# MW5500.net
KiCad netlist of a schematic drawn in Altium Designer
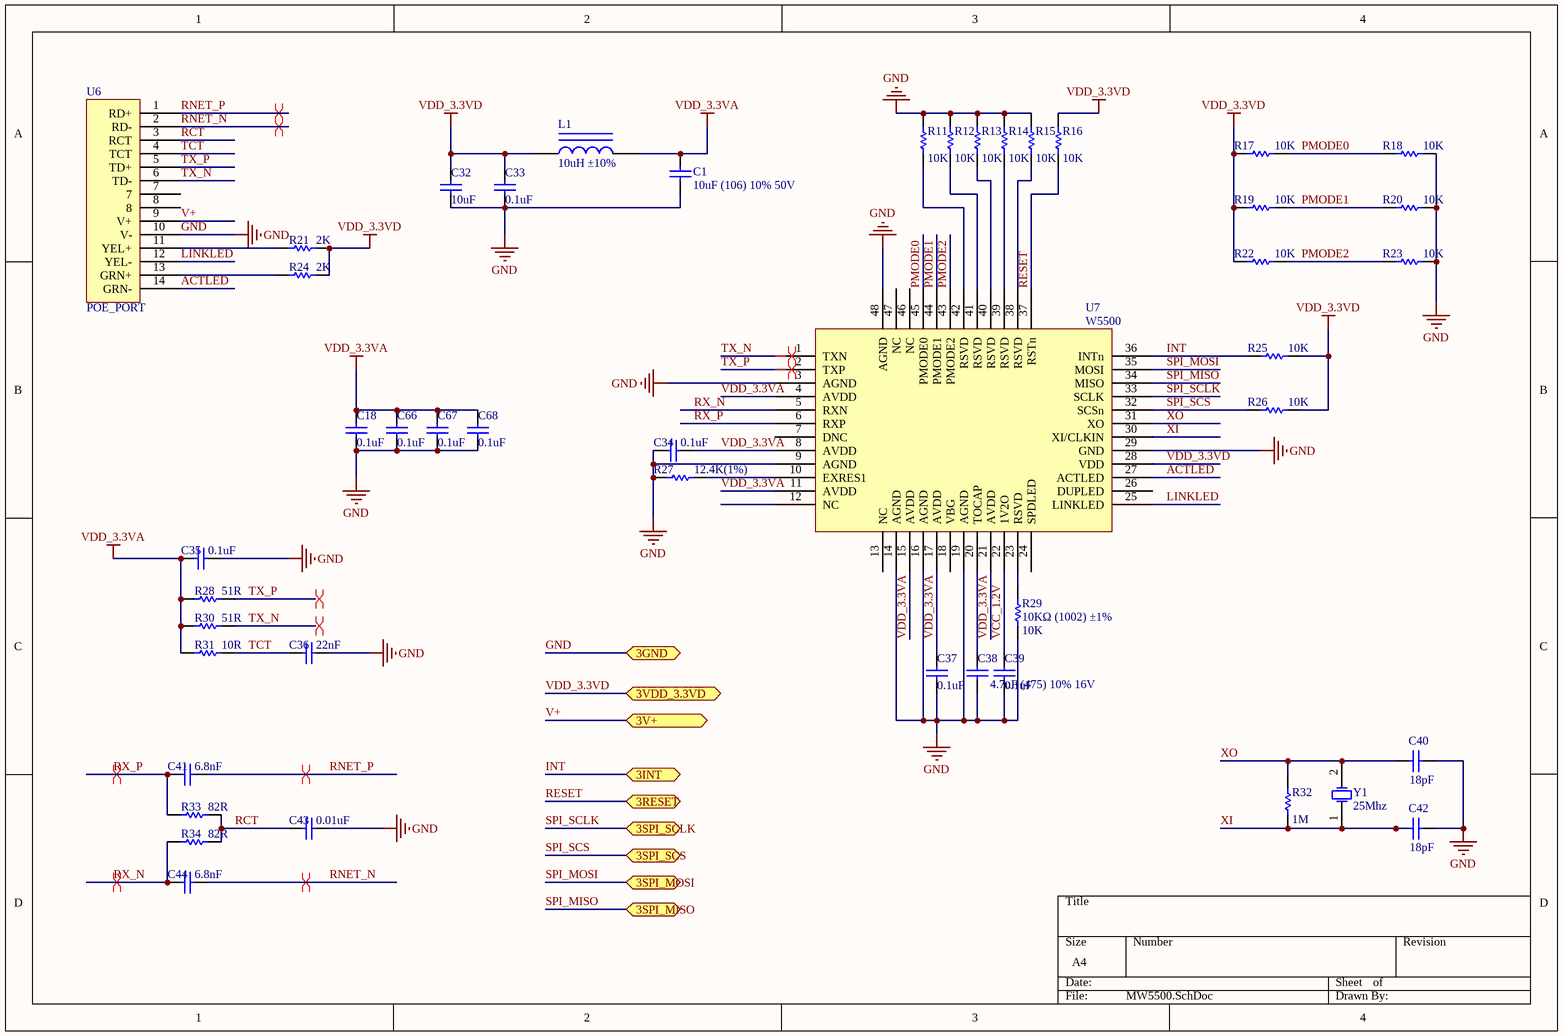
[diagram p0: MW5500.SchDoc]

(export (version "E")
  (design (tool "Eeschema 10.0.6"))
  (components
    (comp (ref "C1")
      (value "10uF (106) 10% 50V")
      (footprint "1206_C")
      (description "贴片电容")
      (libsource (lib "Miscellaneous Devices LC") (part "1206 10uF (106) 10% 50V"))
    )
    (comp (ref "C18")
      (value "0.1uF")
      (footprint "1608[0603]")
      (description "Capacitor")
      (fields (field (name "Comment") "100nF (104) ±10% 50V") (field (name "PUBLISHER") "Altium Limited"))
      (libsource (lib "Miscellaneous Devices") (part "Cap"))
    )
    (comp (ref "C32")
      (value "10uF")
      (footprint "C1206")
      (description "Capacitor")
      (fields (field (name "Comment") "10uF (106) ±10% 50V") (field (name "PUBLISHER") "Altium Limited"))
      (libsource (lib "Miscellaneous Devices") (part "Cap"))
    )
    (comp (ref "C33")
      (value "0.1uF")
      (footprint "1608[0603]")
      (description "Capacitor")
      (fields (field (name "Comment") "100nF (104) ±10% 50V") (field (name "PUBLISHER") "Altium Limited"))
      (libsource (lib "Miscellaneous Devices") (part "Cap"))
    )
    (comp (ref "C34")
      (value "0.1uF")
      (footprint "0805_C")
      (description "Capacitor")
      (fields (field (name "Comment") "100nF (104) ±10% 50V") (field (name "PUBLISHER") "Altium Limited"))
      (libsource (lib "Miscellaneous Devices") (part "Cap"))
    )
    (comp (ref "C35")
      (value "0.1uF")
      (footprint "1608[0603]")
      (description "Capacitor")
      (fields (field (name "Comment") "100nF (104) ±10% 50V") (field (name "PUBLISHER") "Altium Limited"))
      (libsource (lib "Miscellaneous Devices") (part "Cap"))
    )
    (comp (ref "C36")
      (value "22nF")
      (footprint "1608[0603]")
      (description "Capacitor")
      (fields (field (name "Comment") "22nF ±10% 50V") (field (name "PUBLISHER") "Altium Limited"))
      (libsource (lib "Miscellaneous Devices") (part "Cap"))
    )
    (comp (ref "C37")
      (value "0.1uF")
      (footprint "1608[0603]")
      (description "Capacitor")
      (fields (field (name "Comment") "100nF (104) ±10% 50V") (field (name "PUBLISHER") "Altium Limited"))
      (libsource (lib "Miscellaneous Devices") (part "Cap"))
    )
    (comp (ref "C38")
      (value "4.7uF (475) 10% 16V")
      (footprint "0603_C")
      (description "贴片电容")
      (libsource (lib "Miscellaneous Devices LC") (part "0603 4.7uF (475) 10% 16V"))
    )
    (comp (ref "C39")
      (value "0.1uF")
      (footprint "1608[0603]")
      (description "Capacitor")
      (fields (field (name "Comment") "100nF (104) ±10% 50V") (field (name "PUBLISHER") "Altium Limited"))
      (libsource (lib "Miscellaneous Devices") (part "Cap"))
    )
    (comp (ref "C40")
      (value "18pF")
      (footprint "1608[0603]")
      (description "Capacitor")
      (fields (field (name "Comment") "18pF ±10% 50V") (field (name "PUBLISHER") "Altium Limited"))
      (libsource (lib "Miscellaneous Devices") (part "Cap"))
    )
    (comp (ref "C41")
      (value "6.8nF")
      (footprint "1608[0603]")
      (description "Capacitor")
      (fields (field (name "Comment") "6.8nF ±10% 50V") (field (name "PUBLISHER") "Altium Limited"))
      (libsource (lib "Miscellaneous Devices") (part "Cap"))
    )
    (comp (ref "C42")
      (value "18pF")
      (footprint "1608[0603]")
      (description "Capacitor")
      (fields (field (name "Comment") "18pF ±10% 50V") (field (name "PUBLISHER") "Altium Limited"))
      (libsource (lib "Miscellaneous Devices") (part "Cap"))
    )
    (comp (ref "C43")
      (value "0.01uF")
      (footprint "1608[0603]")
      (description "Capacitor")
      (fields (field (name "Comment") "100nF (104) ±10% 50V") (field (name "PUBLISHER") "Altium Limited"))
      (libsource (lib "Miscellaneous Devices") (part "Cap"))
    )
    (comp (ref "C44")
      (value "6.8nF")
      (footprint "1608[0603]")
      (description "Capacitor")
      (fields (field (name "Comment") "6.8nF ±10% 50V") (field (name "PUBLISHER") "Altium Limited"))
      (libsource (lib "Miscellaneous Devices") (part "Cap"))
    )
    (comp (ref "C66")
      (value "0.1uF")
      (footprint "1608[0603]")
      (description "Capacitor")
      (fields (field (name "Comment") "100nF (104) ±10% 50V") (field (name "PUBLISHER") "Altium Limited"))
      (libsource (lib "Miscellaneous Devices") (part "Cap"))
    )
    (comp (ref "C67")
      (value "0.1uF")
      (footprint "1608[0603]")
      (description "Capacitor")
      (fields (field (name "Comment") "100nF (104) ±10% 50V") (field (name "PUBLISHER") "Altium Limited"))
      (libsource (lib "Miscellaneous Devices") (part "Cap"))
    )
    (comp (ref "C68")
      (value "0.1uF")
      (footprint "1608[0603]")
      (description "Capacitor")
      (fields (field (name "Comment") "100nF (104) ±10% 50V") (field (name "PUBLISHER") "Altium Limited"))
      (libsource (lib "Miscellaneous Devices") (part "Cap"))
    )
    (comp (ref "L1")
      (value "10uH ±10%")
      (footprint "1206_L")
      (description "贴片电感")
      (libsource (lib "Miscellaneous Devices LC") (part "1206 10uH 10%"))
    )
    (comp (ref "R11")
      (value "10K")
      (footprint "1608[0603]")
      (description "Resistor")
      (fields (field (name "Comment") "10KΩ (1002) ±1%") (field (name "PUBLISHER") "Altium Limited"))
      (libsource (lib "Miscellaneous Devices") (part "Res1"))
    )
    (comp (ref "R12")
      (value "10K")
      (footprint "1608[0603]")
      (description "Resistor")
      (fields (field (name "Comment") "10KΩ (1002) ±1%") (field (name "PUBLISHER") "Altium Limited"))
      (libsource (lib "Miscellaneous Devices") (part "Res1"))
    )
    (comp (ref "R13")
      (value "10K")
      (footprint "1608[0603]")
      (description "Resistor")
      (fields (field (name "Comment") "10KΩ (1002) ±1%") (field (name "PUBLISHER") "Altium Limited"))
      (libsource (lib "Miscellaneous Devices") (part "Res1"))
    )
    (comp (ref "R14")
      (value "10K")
      (footprint "1608[0603]")
      (description "Resistor")
      (fields (field (name "Comment") "10KΩ (1002) ±1%") (field (name "PUBLISHER") "Altium Limited"))
      (libsource (lib "Miscellaneous Devices") (part "Res1"))
    )
    (comp (ref "R15")
      (value "10K")
      (footprint "1608[0603]")
      (description "Resistor")
      (fields (field (name "Comment") "10KΩ (1002) ±1%") (field (name "PUBLISHER") "Altium Limited"))
      (libsource (lib "Miscellaneous Devices") (part "Res1"))
    )
    (comp (ref "R16")
      (value "10K")
      (footprint "1608[0603]")
      (description "Resistor")
      (fields (field (name "Comment") "10KΩ (1002) ±1%") (field (name "PUBLISHER") "Altium Limited"))
      (libsource (lib "Miscellaneous Devices") (part "Res1"))
    )
    (comp (ref "R17")
      (value "10K")
      (footprint "1608[0603]")
      (description "Resistor")
      (fields (field (name "Comment") "10KΩ (1002) ±1%") (field (name "PUBLISHER") "Altium Limited"))
      (libsource (lib "Miscellaneous Devices") (part "Res1"))
    )
    (comp (ref "R18")
      (value "10K")
      (footprint "1608[0603]")
      (description "Resistor")
      (fields (field (name "Comment") "10KΩ (1002) ±1%") (field (name "PUBLISHER") "Altium Limited"))
      (libsource (lib "Miscellaneous Devices") (part "Res1"))
    )
    (comp (ref "R19")
      (value "10K")
      (footprint "1608[0603]")
      (description "Resistor")
      (fields (field (name "Comment") "10KΩ (1002) ±1%") (field (name "PUBLISHER") "Altium Limited"))
      (libsource (lib "Miscellaneous Devices") (part "Res1"))
    )
    (comp (ref "R20")
      (value "10K")
      (footprint "1608[0603]")
      (description "Resistor")
      (fields (field (name "Comment") "10KΩ (1002) ±1%") (field (name "PUBLISHER") "Altium Limited"))
      (libsource (lib "Miscellaneous Devices") (part "Res1"))
    )
    (comp (ref "R21")
      (value "2K")
      (footprint "1608[0603]")
      (description "Resistor")
      (fields (field (name "Comment") "2KΩ (1001) ±1%") (field (name "PUBLISHER") "Altium Limited"))
      (libsource (lib "Miscellaneous Devices") (part "Res1"))
    )
    (comp (ref "R22")
      (value "10K")
      (footprint "1608[0603]")
      (description "Resistor")
      (fields (field (name "Comment") "10KΩ (1002) ±1%") (field (name "PUBLISHER") "Altium Limited"))
      (libsource (lib "Miscellaneous Devices") (part "Res1"))
    )
    (comp (ref "R23")
      (value "10K")
      (footprint "1608[0603]")
      (description "Resistor")
      (fields (field (name "Comment") "10KΩ (1002) ±1%") (field (name "PUBLISHER") "Altium Limited"))
      (libsource (lib "Miscellaneous Devices") (part "Res1"))
    )
    (comp (ref "R24")
      (value "2K")
      (footprint "1608[0603]")
      (description "Resistor")
      (fields (field (name "Comment") "2KΩ (1001) ±1%") (field (name "PUBLISHER") "Altium Limited"))
      (libsource (lib "Miscellaneous Devices") (part "Res1"))
    )
    (comp (ref "R25")
      (value "10K")
      (footprint "1608[0603]")
      (description "Resistor")
      (fields (field (name "Comment") "10KΩ (1002) ±1%") (field (name "PUBLISHER") "Altium Limited"))
      (libsource (lib "Miscellaneous Devices") (part "Res1"))
    )
    (comp (ref "R26")
      (value "10K")
      (footprint "1608[0603]")
      (description "Resistor")
      (fields (field (name "Comment") "10KΩ (1002) ±1%") (field (name "PUBLISHER") "Altium Limited"))
      (libsource (lib "Miscellaneous Devices") (part "Res1"))
    )
    (comp (ref "R27")
      (value "12.4K(1%)")
      (footprint "1608[0603]")
      (description "Resistor")
      (fields (field (name "Comment") "12.4KΩ   ±1%") (field (name "PUBLISHER") "Altium Limited"))
      (libsource (lib "Miscellaneous Devices") (part "Res1"))
    )
    (comp (ref "R28")
      (value "51R")
      (footprint "1608[0603]")
      (description "Resistor")
      (fields (field (name "Comment") "51Ω (51R0) ±1%") (field (name "PUBLISHER") "Altium Limited"))
      (libsource (lib "Miscellaneous Devices") (part "Res1"))
    )
    (comp (ref "R29")
      (value "10KΩ (1002) ±1%")
      (footprint "1608[0603]")
      (description "Resistor")
      (fields (field (name "ALTIUM_VALUE") "10K") (field (name "PUBLISHER") "Altium Limited"))
      (libsource (lib "Miscellaneous Devices") (part "Res1"))
    )
    (comp (ref "R30")
      (value "51R")
      (footprint "1608[0603]")
      (description "Resistor")
      (fields (field (name "Comment") "51Ω (51R0) ±1%") (field (name "PUBLISHER") "Altium Limited"))
      (libsource (lib "Miscellaneous Devices") (part "Res1"))
    )
    (comp (ref "R31")
      (value "10R")
      (footprint "1608[0603]")
      (description "Resistor")
      (fields (field (name "Comment") "10Ω (10R0) ±1%") (field (name "PUBLISHER") "Altium Limited"))
      (libsource (lib "Miscellaneous Devices") (part "Res1"))
    )
    (comp (ref "R32")
      (value "1M")
      (footprint "1608[0603]")
      (description "Resistor")
      (fields (field (name "Comment") "1MΩ (1004) ±1%") (field (name "PUBLISHER") "Altium Limited"))
      (libsource (lib "Miscellaneous Devices") (part "Res1"))
    )
    (comp (ref "R33")
      (value "82R")
      (footprint "1608[0603]")
      (description "Resistor")
      (fields (field (name "Comment") "82Ω (82R0) ±1%") (field (name "PUBLISHER") "Altium Limited"))
      (libsource (lib "Miscellaneous Devices") (part "Res1"))
    )
    (comp (ref "R34")
      (value "82R")
      (footprint "1608[0603]")
      (description "Resistor")
      (fields (field (name "Comment") "82Ω (82R0) ±1%") (field (name "PUBLISHER") "Altium Limited"))
      (libsource (lib "Miscellaneous Devices") (part "Res1"))
    )
    (comp (ref "U6")
      (value "POE_PORT")
      (footprint "POE_RJ45")
      (libsource (lib "LS_Schlib1") (part "POE_PORT"))
    )
    (comp (ref "U7") (value "W5500") (footprint "LQFP48") (libsource (lib "LS_Schlib1") (part "W5500")))
    (comp (ref "Y1")
      (value "25Mhz")
      (footprint "XTAL")
      (description "Crystal Oscillator")
      (fields (field (name "PUBLISHER") "Altium Limited"))
      (libsource (lib "Miscellaneous Devices") (part "XTAL"))
    )
  )
  (nets
    (net (code "1") (name "/ACTLED") (class "Default")
      (node (ref "U6") (pin "14") (pinfunction "GRN-_14") (pintype "passive"))
      (node (ref "U7") (pin "27") (pinfunction "ACTLED_27") (pintype "passive"))
    )
    (net (code "2") (name "/INT") (class "Default")
      (node (ref "R25") (pin "1") (pinfunction "1_1") (pintype "passive"))
      (node (ref "U7") (pin "36") (pinfunction "INTn_36") (pintype "passive"))
    )
    (net (code "3") (name "/LINKLED") (class "Default")
      (node (ref "U6") (pin "12") (pinfunction "YEL-_12") (pintype "passive"))
      (node (ref "U7") (pin "25") (pinfunction "LINKLED_25") (pintype "passive"))
    )
    (net (code "4") (name "/PMODE0") (class "Default")
      (node (ref "R17") (pin "2") (pinfunction "2_2") (pintype "passive"))
      (node (ref "R18") (pin "1") (pinfunction "1_1") (pintype "passive"))
      (node (ref "U7") (pin "45") (pinfunction "PMODE0_45") (pintype "passive"))
    )
    (net (code "5") (name "/PMODE1") (class "Default")
      (node (ref "R19") (pin "2") (pinfunction "2_2") (pintype "passive"))
      (node (ref "R20") (pin "1") (pinfunction "1_1") (pintype "passive"))
      (node (ref "U7") (pin "44") (pinfunction "PMODE1_44") (pintype "passive"))
    )
    (net (code "6") (name "/PMODE2") (class "Default")
      (node (ref "R22") (pin "2") (pinfunction "2_2") (pintype "passive"))
      (node (ref "R23") (pin "1") (pinfunction "1_1") (pintype "passive"))
      (node (ref "U7") (pin "43") (pinfunction "PMODE2_43") (pintype "passive"))
    )
    (net (code "7") (name "/RCT") (class "Default")
      (node (ref "C43") (pin "1") (pinfunction "1_1") (pintype "passive"))
      (node (ref "R33") (pin "2") (pinfunction "2_2") (pintype "passive"))
      (node (ref "R34") (pin "2") (pinfunction "2_2") (pintype "passive"))
      (node (ref "U6") (pin "3") (pinfunction "RCT_3") (pintype "passive"))
    )
    (net (code "8") (name "/RESET") (class "Default")
      (node (ref "R16") (pin "1") (pinfunction "1_1") (pintype "passive"))
      (node (ref "U7") (pin "37") (pinfunction "RSTn_37") (pintype "passive"))
    )
    (net (code "9") (name "/RNET_N") (class "Default")
      (node (ref "C44") (pin "2") (pinfunction "2_2") (pintype "passive"))
      (node (ref "U6") (pin "2") (pinfunction "RD-_2") (pintype "passive"))
    )
    (net (code "10") (name "/RNET_P") (class "Default")
      (node (ref "C41") (pin "2") (pinfunction "2_2") (pintype "passive"))
      (node (ref "U6") (pin "1") (pinfunction "RD+_1") (pintype "passive"))
    )
    (net (code "11") (name "/RX_N") (class "Default")
      (node (ref "C44") (pin "1") (pinfunction "1_1") (pintype "passive"))
      (node (ref "R34") (pin "1") (pinfunction "1_1") (pintype "passive"))
      (node (ref "U7") (pin "5") (pinfunction "RXN_5") (pintype "passive"))
    )
    (net (code "12") (name "/RX_P") (class "Default")
      (node (ref "C41") (pin "1") (pinfunction "1_1") (pintype "passive"))
      (node (ref "R33") (pin "1") (pinfunction "1_1") (pintype "passive"))
      (node (ref "U7") (pin "6") (pinfunction "RXP_6") (pintype "passive"))
    )
    (net (code "13") (name "/SPI_MISO") (class "Default")
      (node (ref "U7") (pin "34") (pinfunction "MISO_34") (pintype "passive"))
    )
    (net (code "14") (name "/SPI_MOSI") (class "Default")
      (node (ref "U7") (pin "35") (pinfunction "MOSI_35") (pintype "passive"))
    )
    (net (code "15") (name "/SPI_SCLK") (class "Default")
      (node (ref "U7") (pin "33") (pinfunction "SCLK_33") (pintype "passive"))
    )
    (net (code "16") (name "/SPI_SCS") (class "Default")
      (node (ref "R26") (pin "1") (pinfunction "1_1") (pintype "passive"))
      (node (ref "U7") (pin "32") (pinfunction "SCSn_32") (pintype "passive"))
    )
    (net (code "17") (name "/TCT") (class "Default")
      (node (ref "C36") (pin "1") (pinfunction "1_1") (pintype "passive"))
      (node (ref "R31") (pin "2") (pinfunction "2_2") (pintype "passive"))
      (node (ref "U6") (pin "4") (pinfunction "TCT_4") (pintype "passive"))
    )
    (net (code "18") (name "/TX_N") (class "Default")
      (node (ref "R30") (pin "2") (pinfunction "2_2") (pintype "passive"))
      (node (ref "U6") (pin "6") (pinfunction "TD-_6") (pintype "passive"))
      (node (ref "U7") (pin "1") (pinfunction "TXN_1") (pintype "passive"))
    )
    (net (code "19") (name "/TX_P") (class "Default")
      (node (ref "R28") (pin "2") (pinfunction "2_2") (pintype "passive"))
      (node (ref "U6") (pin "5") (pinfunction "TD+_5") (pintype "passive"))
      (node (ref "U7") (pin "2") (pinfunction "TXP_2") (pintype "passive"))
    )
    (net (code "20") (name "/V+") (class "Default")
      (node (ref "U6") (pin "9") (pinfunction "V+_9") (pintype "passive"))
    )
    (net (code "21") (name "/VCC_1.2V") (class "Default")
      (node (ref "C39") (pin "2") (pinfunction "2_2") (pintype "passive"))
      (node (ref "U7") (pin "22") (pinfunction "1V2O_22") (pintype "passive"))
    )
    (net (code "22") (name "/XI") (class "Default")
      (node (ref "C42") (pin "2") (pinfunction "2_2") (pintype "passive"))
      (node (ref "R32") (pin "1") (pinfunction "1_1") (pintype "passive"))
      (node (ref "U7") (pin "30") (pinfunction "XI/CLKIN_30") (pintype "passive"))
      (node (ref "Y1") (pin "1") (pinfunction "OSC1_1") (pintype "passive"))
    )
    (net (code "23") (name "/XO") (class "Default")
      (node (ref "C40") (pin "2") (pinfunction "2_2") (pintype "passive"))
      (node (ref "R32") (pin "2") (pinfunction "2_2") (pintype "passive"))
      (node (ref "U7") (pin "31") (pinfunction "XO_31") (pintype "passive"))
      (node (ref "Y1") (pin "2") (pinfunction "OSC2_2") (pintype "passive"))
    )
    (net (code "24") (name "GND") (class "Default")
      (node (ref "C1") (pin "1") (pinfunction "1_1") (pintype "passive"))
      (node (ref "C18") (pin "1") (pinfunction "1_1") (pintype "passive"))
      (node (ref "C32") (pin "1") (pinfunction "1_1") (pintype "passive"))
      (node (ref "C33") (pin "1") (pinfunction "1_1") (pintype "passive"))
      (node (ref "C34") (pin "1") (pinfunction "1_1") (pintype "passive"))
      (node (ref "C35") (pin "2") (pinfunction "2_2") (pintype "passive"))
      (node (ref "C36") (pin "2") (pinfunction "2_2") (pintype "passive"))
      (node (ref "C37") (pin "1") (pinfunction "1_1") (pintype "passive"))
      (node (ref "C38") (pin "1") (pinfunction "1_1") (pintype "passive"))
      (node (ref "C39") (pin "1") (pinfunction "1_1") (pintype "passive"))
      (node (ref "C40") (pin "1") (pinfunction "1_1") (pintype "passive"))
      (node (ref "C42") (pin "1") (pinfunction "1_1") (pintype "passive"))
      (node (ref "C43") (pin "2") (pinfunction "2_2") (pintype "passive"))
      (node (ref "C66") (pin "1") (pinfunction "1_1") (pintype "passive"))
      (node (ref "C67") (pin "1") (pinfunction "1_1") (pintype "passive"))
      (node (ref "C68") (pin "1") (pinfunction "1_1") (pintype "passive"))
      (node (ref "R11") (pin "2") (pinfunction "2_2") (pintype "passive"))
      (node (ref "R12") (pin "2") (pinfunction "2_2") (pintype "passive"))
      (node (ref "R13") (pin "2") (pinfunction "2_2") (pintype "passive"))
      (node (ref "R14") (pin "2") (pinfunction "2_2") (pintype "passive"))
      (node (ref "R15") (pin "2") (pinfunction "2_2") (pintype "passive"))
      (node (ref "R18") (pin "2") (pinfunction "2_2") (pintype "passive"))
      (node (ref "R20") (pin "2") (pinfunction "2_2") (pintype "passive"))
      (node (ref "R23") (pin "2") (pinfunction "2_2") (pintype "passive"))
      (node (ref "R27") (pin "1") (pinfunction "1_1") (pintype "passive"))
      (node (ref "R29") (pin "1") (pinfunction "1_1") (pintype "passive"))
      (node (ref "U6") (pin "10") (pinfunction "V-_10") (pintype "passive"))
      (node (ref "U7") (pin "14") (pinfunction "AGND_14") (pintype "passive"))
      (node (ref "U7") (pin "16") (pinfunction "AGND_16") (pintype "passive"))
      (node (ref "U7") (pin "19") (pinfunction "AGND_19") (pintype "passive"))
      (node (ref "U7") (pin "29") (pinfunction "GND_29") (pintype "passive"))
      (node (ref "U7") (pin "3") (pinfunction "AGND_3") (pintype "passive"))
      (node (ref "U7") (pin "48") (pinfunction "AGND_48") (pintype "passive"))
      (node (ref "U7") (pin "9") (pinfunction "AGND_9") (pintype "passive"))
    )
    (net (code "25") (name "Net-(R11-Pad1)") (class "Default")
      (node (ref "R11") (pin "1") (pinfunction "1_1") (pintype "passive"))
      (node (ref "U7") (pin "42") (pinfunction "RSVD_42") (pintype "passive"))
    )
    (net (code "26") (name "Net-(R12-Pad1)") (class "Default")
      (node (ref "R12") (pin "1") (pinfunction "1_1") (pintype "passive"))
      (node (ref "U7") (pin "41") (pinfunction "RSVD_41") (pintype "passive"))
    )
    (net (code "27") (name "Net-(R13-Pad1)") (class "Default")
      (node (ref "R13") (pin "1") (pinfunction "1_1") (pintype "passive"))
      (node (ref "U7") (pin "40") (pinfunction "RSVD_40") (pintype "passive"))
    )
    (net (code "28") (name "Net-(R14-Pad1)") (class "Default")
      (node (ref "R14") (pin "1") (pinfunction "1_1") (pintype "passive"))
      (node (ref "U7") (pin "39") (pinfunction "RSVD_39") (pintype "passive"))
    )
    (net (code "29") (name "Net-(R15-Pad1)") (class "Default")
      (node (ref "R15") (pin "1") (pinfunction "1_1") (pintype "passive"))
      (node (ref "U7") (pin "38") (pinfunction "RSVD_38") (pintype "passive"))
    )
    (net (code "30") (name "Net-(R29-Pad2)") (class "Default")
      (node (ref "R29") (pin "2") (pinfunction "2_2") (pintype "passive"))
      (node (ref "U7") (pin "23") (pinfunction "RSVD_23") (pintype "passive"))
    )
    (net (code "31") (name "Net-(U6-GRN+)") (class "Default")
      (node (ref "R24") (pin "1") (pinfunction "1_1") (pintype "passive"))
      (node (ref "U6") (pin "13") (pinfunction "GRN+_13") (pintype "passive"))
    )
    (net (code "32") (name "Net-(U6-YEL+)") (class "Default")
      (node (ref "R21") (pin "1") (pinfunction "1_1") (pintype "passive"))
      (node (ref "U6") (pin "11") (pinfunction "YEL+_11") (pintype "passive"))
    )
    (net (code "33") (name "Net-(U7-EXRES1)") (class "Default")
      (node (ref "R27") (pin "2") (pinfunction "2_2") (pintype "passive"))
      (node (ref "U7") (pin "10") (pinfunction "EXRES1_10") (pintype "passive"))
    )
    (net (code "34") (name "Net-(U7-TOCAP)") (class "Default")
      (node (ref "C38") (pin "2") (pinfunction "2_2") (pintype "passive"))
      (node (ref "U7") (pin "20") (pinfunction "TOCAP_20") (pintype "passive"))
    )
    (net (code "35") (name "VDD_3.3VA") (class "Default")
      (node (ref "C1") (pin "2") (pinfunction "2_2") (pintype "passive"))
      (node (ref "C18") (pin "2") (pinfunction "2_2") (pintype "passive"))
      (node (ref "C34") (pin "2") (pinfunction "2_2") (pintype "passive"))
      (node (ref "C35") (pin "1") (pinfunction "1_1") (pintype "passive"))
      (node (ref "C37") (pin "2") (pinfunction "2_2") (pintype "passive"))
      (node (ref "C66") (pin "2") (pinfunction "2_2") (pintype "passive"))
      (node (ref "C67") (pin "2") (pinfunction "2_2") (pintype "passive"))
      (node (ref "C68") (pin "2") (pinfunction "2_2") (pintype "passive"))
      (node (ref "L1") (pin "2") (pinfunction "2_2") (pintype "passive"))
      (node (ref "R28") (pin "1") (pinfunction "1_1") (pintype "passive"))
      (node (ref "R30") (pin "1") (pinfunction "1_1") (pintype "passive"))
      (node (ref "R31") (pin "1") (pinfunction "1_1") (pintype "passive"))
      (node (ref "U7") (pin "11") (pinfunction "AVDD_11") (pintype "passive"))
      (node (ref "U7") (pin "15") (pinfunction "AVDD_15") (pintype "passive"))
      (node (ref "U7") (pin "17") (pinfunction "AVDD_17") (pintype "passive"))
      (node (ref "U7") (pin "21") (pinfunction "AVDD_21") (pintype "passive"))
      (node (ref "U7") (pin "4") (pinfunction "AVDD_4") (pintype "passive"))
      (node (ref "U7") (pin "8") (pinfunction "AVDD_8") (pintype "passive"))
    )
    (net (code "36") (name "VDD_3.3VD") (class "Default")
      (node (ref "C32") (pin "2") (pinfunction "2_2") (pintype "passive"))
      (node (ref "C33") (pin "2") (pinfunction "2_2") (pintype "passive"))
      (node (ref "L1") (pin "1") (pinfunction "1_1") (pintype "passive"))
      (node (ref "R16") (pin "2") (pinfunction "2_2") (pintype "passive"))
      (node (ref "R17") (pin "1") (pinfunction "1_1") (pintype "passive"))
      (node (ref "R19") (pin "1") (pinfunction "1_1") (pintype "passive"))
      (node (ref "R21") (pin "2") (pinfunction "2_2") (pintype "passive"))
      (node (ref "R22") (pin "1") (pinfunction "1_1") (pintype "passive"))
      (node (ref "R24") (pin "2") (pinfunction "2_2") (pintype "passive"))
      (node (ref "R25") (pin "2") (pinfunction "2_2") (pintype "passive"))
      (node (ref "R26") (pin "2") (pinfunction "2_2") (pintype "passive"))
      (node (ref "U7") (pin "28") (pinfunction "VDD_28") (pintype "passive"))
    )
    (net (code "37") (name "unconnected-(U6-Pad7)") (class "Default")
      (node (ref "U6") (pin "7") (pinfunction "7_7") (pintype "passive"))
    )
    (net (code "38") (name "unconnected-(U6-Pad8)") (class "Default")
      (node (ref "U6") (pin "8") (pinfunction "8_8") (pintype "passive"))
    )
    (net (code "39") (name "unconnected-(U7-DNC-Pad7)") (class "Default")
      (node (ref "U7") (pin "7") (pinfunction "DNC_7") (pintype "passive"))
    )
    (net (code "40") (name "unconnected-(U7-DUPLED-Pad26)") (class "Default")
      (node (ref "U7") (pin "26") (pinfunction "DUPLED_26") (pintype "passive"))
    )
    (net (code "41") (name "unconnected-(U7-NC-Pad12)") (class "Default")
      (node (ref "U7") (pin "12") (pinfunction "NC_12") (pintype "passive"))
    )
    (net (code "42") (name "unconnected-(U7-NC-Pad13)") (class "Default")
      (node (ref "U7") (pin "13") (pinfunction "NC_13") (pintype "passive"))
    )
    (net (code "43") (name "unconnected-(U7-NC-Pad46)") (class "Default")
      (node (ref "U7") (pin "46") (pinfunction "NC_46") (pintype "passive"))
    )
    (net (code "44") (name "unconnected-(U7-NC-Pad47)") (class "Default")
      (node (ref "U7") (pin "47") (pinfunction "NC_47") (pintype "passive"))
    )
    (net (code "45") (name "unconnected-(U7-SPDLED-Pad24)") (class "Default")
      (node (ref "U7") (pin "24") (pinfunction "SPDLED_24") (pintype "passive"))
    )
    (net (code "46") (name "unconnected-(U7-VBG-Pad18)") (class "Default")
      (node (ref "U7") (pin "18") (pinfunction "VBG_18") (pintype "passive"))
    )
  )
)
